# LCD_to_VGA_Modul.net
KiCad netlist of a schematic drawn in EAGLE
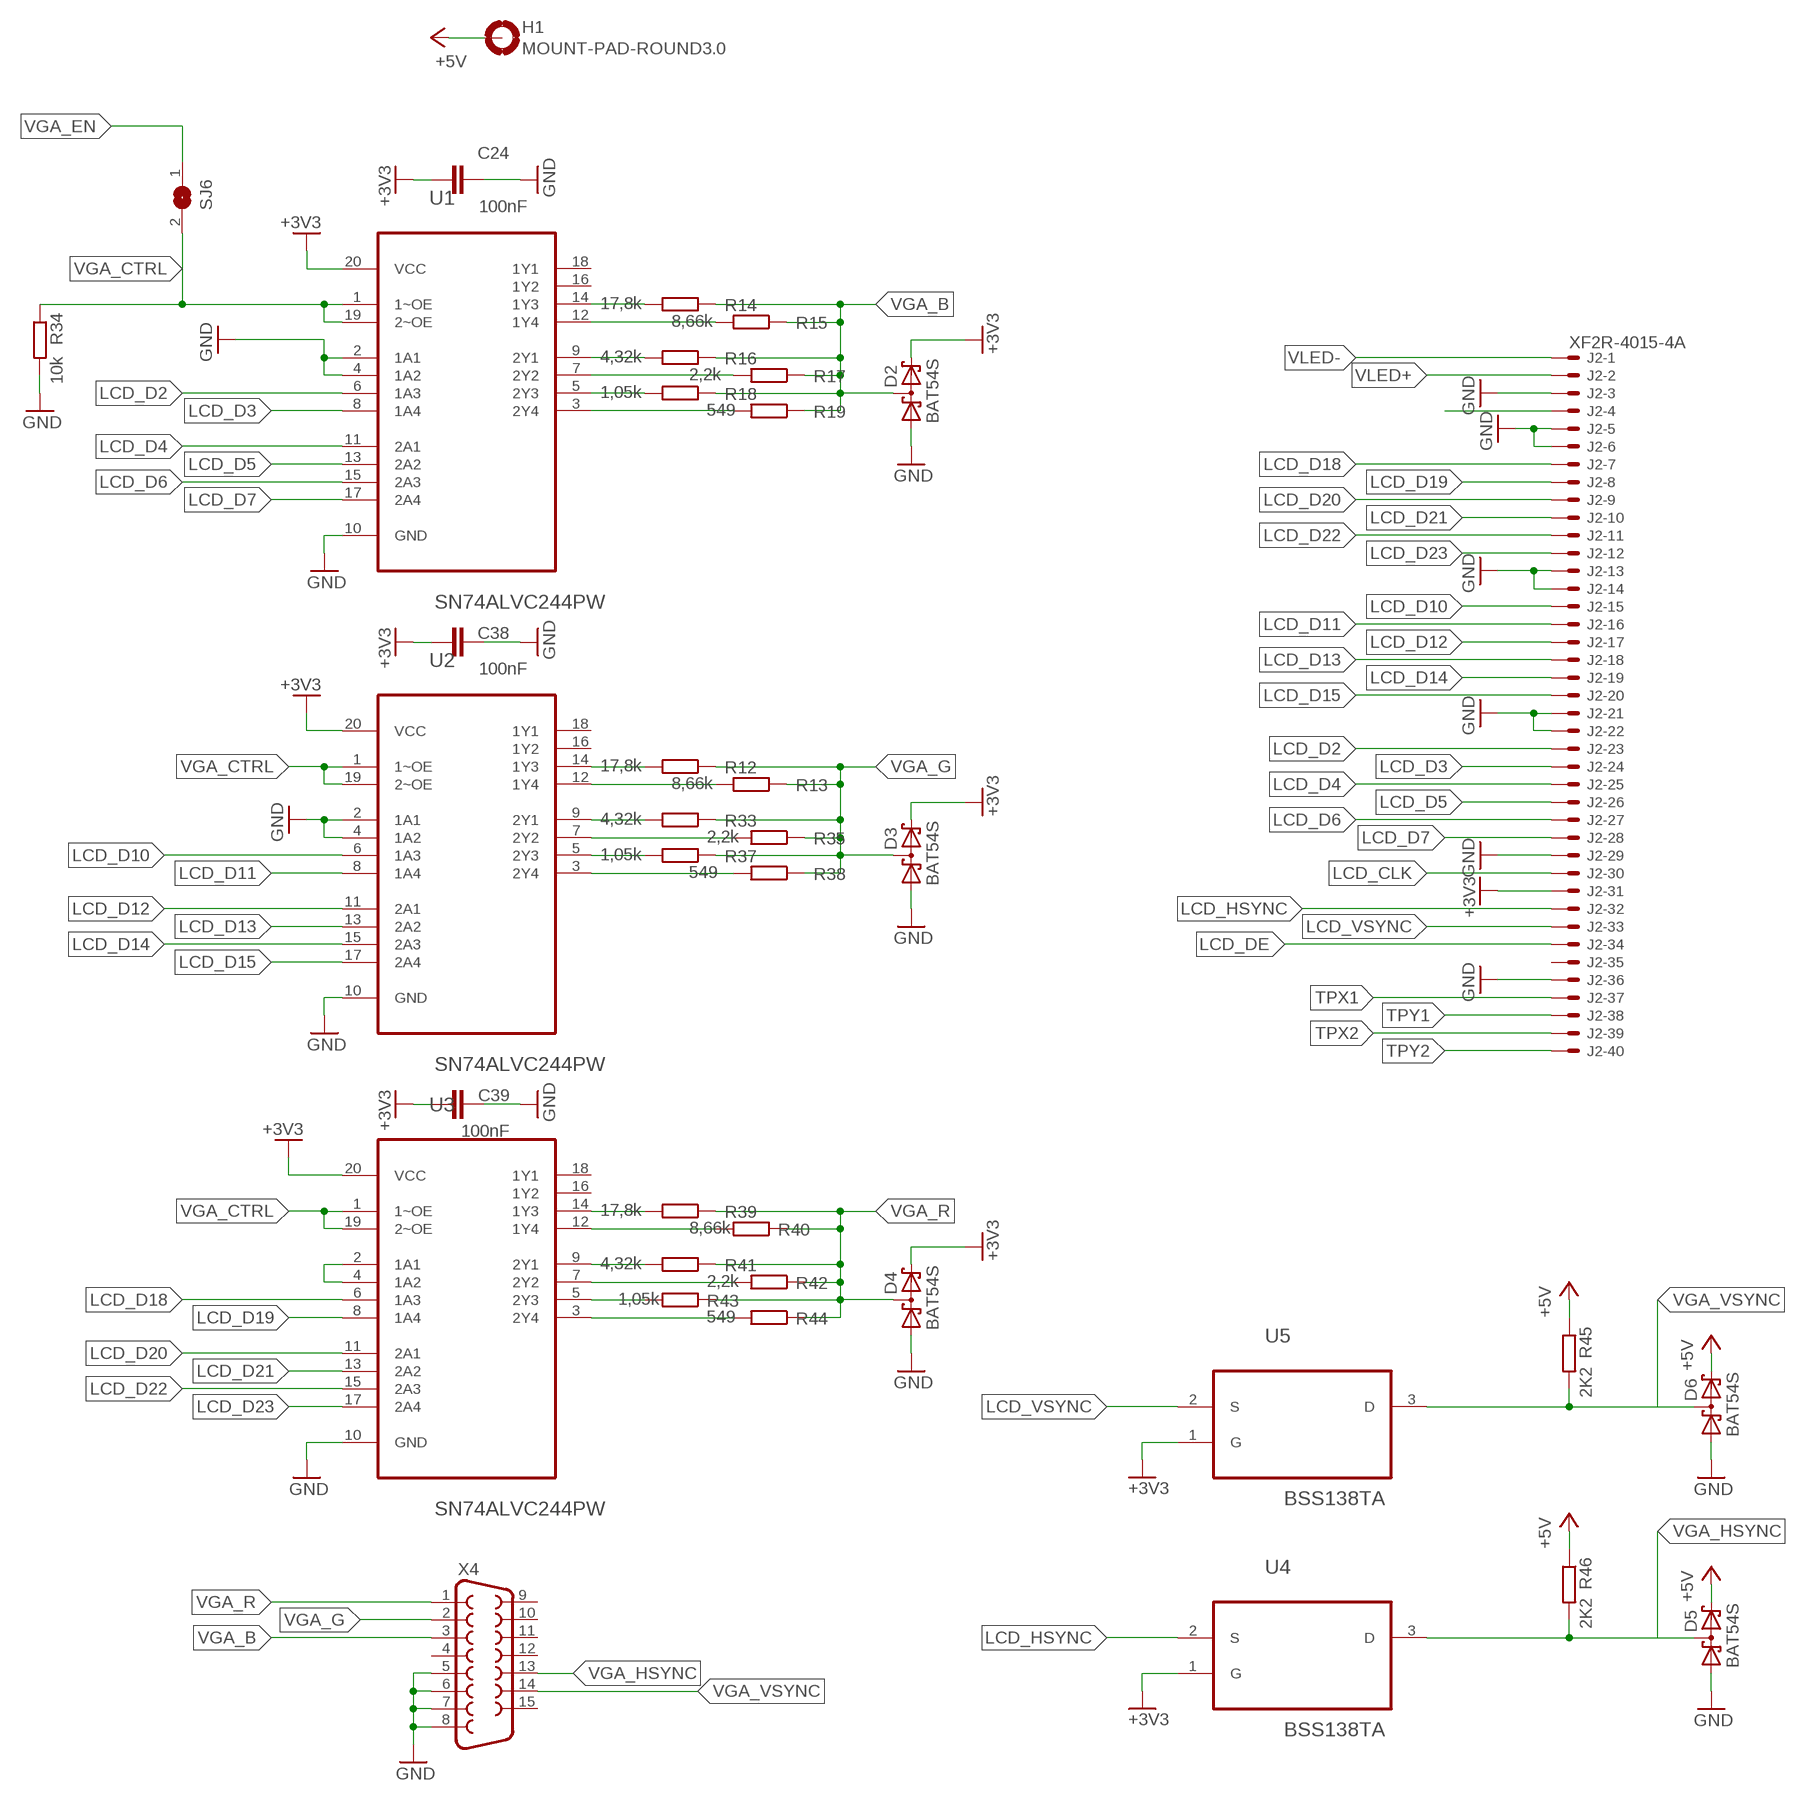
[diagram p0: schematic, sheet 1]

(export (version "E")
  (design (tool "Eeschema 10.0.6"))
  (components
    (comp (ref "C24")
      (value "100nF")
      (footprint "eagle-import:C0805")
      (libsource (lib "eagle-import") (part "C-EUC0805"))
    )
    (comp (ref "C38")
      (value "100nF")
      (footprint "eagle-import:C0805")
      (libsource (lib "eagle-import") (part "C-EUC0805"))
    )
    (comp (ref "C39")
      (value "100nF")
      (footprint "eagle-import:C0805")
      (libsource (lib "eagle-import") (part "C-EUC0805"))
    )
    (comp (ref "D2")
      (value "BAT54S")
      (footprint "eagle-import:SOT23")
      (libsource (lib "eagle-import") (part "BAT54S"))
    )
    (comp (ref "D3")
      (value "BAT54S")
      (footprint "eagle-import:SOT23")
      (libsource (lib "eagle-import") (part "BAT54S"))
    )
    (comp (ref "D4")
      (value "BAT54S")
      (footprint "eagle-import:SOT23")
      (libsource (lib "eagle-import") (part "BAT54S"))
    )
    (comp (ref "D5")
      (value "BAT54S")
      (footprint "eagle-import:SOT23")
      (libsource (lib "eagle-import") (part "BAT54S"))
    )
    (comp (ref "D6")
      (value "BAT54S")
      (footprint "eagle-import:SOT23")
      (libsource (lib "eagle-import") (part "BAT54S"))
    )
    (comp (ref "H1")
      (value "MOUNT-PAD-ROUND3.0")
      (footprint "eagle-import:3,0-PAD")
      (libsource (lib "eagle-import") (part "MOUNT-PAD-ROUND3.0"))
    )
    (comp (ref "J2")
      (value "XF2R-4015-4A")
      (footprint "eagle-import:XF2R-4015-4A")
      (libsource (lib "eagle-import") (part "XF2-40?15-4AR"))
    )
    (comp (ref "R12")
      (value "17,8k")
      (footprint "eagle-import:R0805")
      (libsource (lib "eagle-import") (part "R-EU_R0805"))
    )
    (comp (ref "R13")
      (value "8,66k")
      (footprint "eagle-import:R0805")
      (libsource (lib "eagle-import") (part "R-EU_R0805"))
    )
    (comp (ref "R14")
      (value "17,8k")
      (footprint "eagle-import:R0805")
      (libsource (lib "eagle-import") (part "R-EU_R0805"))
    )
    (comp (ref "R15")
      (value "8,66k")
      (footprint "eagle-import:R0805")
      (libsource (lib "eagle-import") (part "R-EU_R0805"))
    )
    (comp (ref "R16")
      (value "4,32k")
      (footprint "eagle-import:R0805")
      (libsource (lib "eagle-import") (part "R-EU_R0805"))
    )
    (comp (ref "R17")
      (value "2,2k")
      (footprint "eagle-import:R0805")
      (libsource (lib "eagle-import") (part "R-EU_R0805"))
    )
    (comp (ref "R18")
      (value "1,05k")
      (footprint "eagle-import:R0805")
      (libsource (lib "eagle-import") (part "R-EU_R0805"))
    )
    (comp (ref "R19")
      (value "549")
      (footprint "eagle-import:R0805")
      (libsource (lib "eagle-import") (part "R-EU_R0805"))
    )
    (comp (ref "R33")
      (value "4,32k")
      (footprint "eagle-import:R0805")
      (libsource (lib "eagle-import") (part "R-EU_R0805"))
    )
    (comp (ref "R34")
      (value "10k")
      (footprint "eagle-import:R0805")
      (libsource (lib "eagle-import") (part "R-EU_R0805"))
    )
    (comp (ref "R35")
      (value "2,2k")
      (footprint "eagle-import:R0805")
      (libsource (lib "eagle-import") (part "R-EU_R0805"))
    )
    (comp (ref "R37")
      (value "1,05k")
      (footprint "eagle-import:R0805")
      (libsource (lib "eagle-import") (part "R-EU_R0805"))
    )
    (comp (ref "R38")
      (value "549")
      (footprint "eagle-import:R0805")
      (libsource (lib "eagle-import") (part "R-EU_R0805"))
    )
    (comp (ref "R39")
      (value "17,8k")
      (footprint "eagle-import:R0805")
      (libsource (lib "eagle-import") (part "R-EU_R0805"))
    )
    (comp (ref "R40")
      (value "8,66k")
      (footprint "eagle-import:R0805")
      (libsource (lib "eagle-import") (part "R-EU_R0805"))
    )
    (comp (ref "R41")
      (value "4,32k")
      (footprint "eagle-import:R0805")
      (libsource (lib "eagle-import") (part "R-EU_R0805"))
    )
    (comp (ref "R42")
      (value "2,2k")
      (footprint "eagle-import:R0805")
      (libsource (lib "eagle-import") (part "R-EU_R0805"))
    )
    (comp (ref "R43")
      (value "1,05k")
      (footprint "eagle-import:R0805")
      (libsource (lib "eagle-import") (part "R-EU_R0805"))
    )
    (comp (ref "R44")
      (value "549")
      (footprint "eagle-import:R0805")
      (libsource (lib "eagle-import") (part "R-EU_R0805"))
    )
    (comp (ref "R45")
      (value "2K2")
      (footprint "eagle-import:R0805")
      (libsource (lib "eagle-import") (part "R-EU_R0805"))
    )
    (comp (ref "R46")
      (value "2K2")
      (footprint "eagle-import:R0805")
      (libsource (lib "eagle-import") (part "R-EU_R0805"))
    )
    (comp (ref "SJ6") (value "SJ") (footprint "eagle-import:SJ") (libsource (lib "eagle-import") (part "SJ")))
    (comp (ref "U1")
      (value "SN74ALVC244PW")
      (footprint "eagle-import:SOP65P640X120-20N")
      (libsource (lib "eagle-import") (part "SN74ALVC244PW"))
    )
    (comp (ref "U2")
      (value "SN74ALVC244PW")
      (footprint "eagle-import:SOP65P640X120-20N")
      (libsource (lib "eagle-import") (part "SN74ALVC244PW"))
    )
    (comp (ref "U3")
      (value "SN74ALVC244PW")
      (footprint "eagle-import:SOP65P640X120-20N")
      (libsource (lib "eagle-import") (part "SN74ALVC244PW"))
    )
    (comp (ref "U4")
      (value "BSS138TA")
      (footprint "eagle-import:SOT95P240X110-3N")
      (libsource (lib "eagle-import") (part "BSS138TA"))
    )
    (comp (ref "U5")
      (value "BSS138TA")
      (footprint "eagle-import:SOT95P240X110-3N")
      (libsource (lib "eagle-import") (part "BSS138TA"))
    )
    (comp (ref "X4")
      (value "F15H")
      (footprint "eagle-import:F15H")
      (libsource (lib "eagle-import") (part "F15H"))
    )
  )
  (nets
    (net (code "1") (name "+3V3") (class "Default")
      (node (ref "C24") (pin "2") (pinfunction "2_2") (pintype "passive"))
      (node (ref "C38") (pin "2") (pinfunction "2_2") (pintype "passive"))
      (node (ref "C39") (pin "2") (pinfunction "2_2") (pintype "passive"))
      (node (ref "D2") (pin "2") (pinfunction "K2_2") (pintype "passive"))
      (node (ref "D3") (pin "2") (pinfunction "K2_2") (pintype "passive"))
      (node (ref "D4") (pin "2") (pinfunction "K2_2") (pintype "passive"))
      (node (ref "J2") (pin "31") (pinfunction "MS_31") (pintype "passive"))
      (node (ref "U1") (pin "20") (pinfunction "VCC_20") (pintype "power_in"))
      (node (ref "U2") (pin "20") (pinfunction "VCC_20") (pintype "power_in"))
      (node (ref "U3") (pin "20") (pinfunction "VCC_20") (pintype "power_in"))
      (node (ref "U4") (pin "1") (pinfunction "G_1") (pintype "passive"))
      (node (ref "U5") (pin "1") (pinfunction "G_1") (pintype "passive"))
    )
    (net (code "2") (name "+5V") (class "Default")
      (node (ref "D5") (pin "2") (pinfunction "K2_2") (pintype "passive"))
      (node (ref "D6") (pin "2") (pinfunction "K2_2") (pintype "passive"))
      (node (ref "H1") (pin "B3,0") (pinfunction "MOUNT_B3,0") (pintype "passive"))
      (node (ref "R45") (pin "1") (pinfunction "1_1") (pintype "passive"))
      (node (ref "R46") (pin "1") (pinfunction "1_1") (pintype "passive"))
    )
    (net (code "3") (name "GND") (class "Default")
      (node (ref "C24") (pin "1") (pinfunction "1_1") (pintype "passive"))
      (node (ref "C38") (pin "1") (pinfunction "1_1") (pintype "passive"))
      (node (ref "C39") (pin "1") (pinfunction "1_1") (pintype "passive"))
      (node (ref "D2") (pin "1") (pinfunction "A1_1") (pintype "passive"))
      (node (ref "D3") (pin "1") (pinfunction "A1_1") (pintype "passive"))
      (node (ref "D4") (pin "1") (pinfunction "A1_1") (pintype "passive"))
      (node (ref "D5") (pin "1") (pinfunction "A1_1") (pintype "passive"))
      (node (ref "D6") (pin "1") (pinfunction "A1_1") (pintype "passive"))
      (node (ref "J2") (pin "13") (pinfunction "MS_13") (pintype "passive"))
      (node (ref "J2") (pin "14") (pinfunction "MS_14") (pintype "passive"))
      (node (ref "J2") (pin "21") (pinfunction "MS_21") (pintype "passive"))
      (node (ref "J2") (pin "22") (pinfunction "MS_22") (pintype "passive"))
      (node (ref "J2") (pin "29") (pinfunction "MS_29") (pintype "passive"))
      (node (ref "J2") (pin "3") (pinfunction "MS_3") (pintype "passive"))
      (node (ref "J2") (pin "36") (pinfunction "MS_36") (pintype "passive"))
      (node (ref "J2") (pin "5") (pinfunction "MS_5") (pintype "passive"))
      (node (ref "J2") (pin "6") (pinfunction "MS_6") (pintype "passive"))
      (node (ref "R34") (pin "2") (pinfunction "2_2") (pintype "passive"))
      (node (ref "U1") (pin "10") (pinfunction "GND_10") (pintype "passive"))
      (node (ref "U1") (pin "2") (pinfunction "1A1_2") (pintype "input"))
      (node (ref "U1") (pin "4") (pinfunction "1A2_4") (pintype "input"))
      (node (ref "U2") (pin "10") (pinfunction "GND_10") (pintype "passive"))
      (node (ref "U2") (pin "2") (pinfunction "1A1_2") (pintype "input"))
      (node (ref "U2") (pin "4") (pinfunction "1A2_4") (pintype "input"))
      (node (ref "U3") (pin "10") (pinfunction "GND_10") (pintype "passive"))
      (node (ref "X4") (pin "5") (pinfunction "5_5") (pintype "passive"))
      (node (ref "X4") (pin "6") (pinfunction "6_6") (pintype "passive"))
      (node (ref "X4") (pin "7") (pinfunction "7_7") (pintype "passive"))
      (node (ref "X4") (pin "8") (pinfunction "8_8") (pintype "passive"))
    )
    (net (code "4") (name "LCD_CLK") (class "Default")
      (node (ref "J2") (pin "30") (pinfunction "MS_30") (pintype "passive"))
    )
    (net (code "5") (name "LCD_D2") (class "Default")
      (node (ref "J2") (pin "23") (pinfunction "MS_23") (pintype "passive"))
      (node (ref "U1") (pin "6") (pinfunction "1A3_6") (pintype "input"))
    )
    (net (code "6") (name "LCD_D3") (class "Default")
      (node (ref "J2") (pin "24") (pinfunction "MS_24") (pintype "passive"))
      (node (ref "U1") (pin "8") (pinfunction "1A4_8") (pintype "input"))
    )
    (net (code "7") (name "LCD_D4") (class "Default")
      (node (ref "J2") (pin "25") (pinfunction "MS_25") (pintype "passive"))
      (node (ref "U1") (pin "11") (pinfunction "2A1_11") (pintype "input"))
    )
    (net (code "8") (name "LCD_D5") (class "Default")
      (node (ref "J2") (pin "26") (pinfunction "MS_26") (pintype "passive"))
      (node (ref "U1") (pin "13") (pinfunction "2A2_13") (pintype "input"))
    )
    (net (code "9") (name "LCD_D6") (class "Default")
      (node (ref "J2") (pin "27") (pinfunction "MS_27") (pintype "passive"))
      (node (ref "U1") (pin "15") (pinfunction "2A3_15") (pintype "input"))
    )
    (net (code "10") (name "LCD_D7") (class "Default")
      (node (ref "J2") (pin "28") (pinfunction "MS_28") (pintype "passive"))
      (node (ref "U1") (pin "17") (pinfunction "2A4_17") (pintype "input"))
    )
    (net (code "11") (name "LCD_D10") (class "Default")
      (node (ref "J2") (pin "15") (pinfunction "MS_15") (pintype "passive"))
      (node (ref "U2") (pin "6") (pinfunction "1A3_6") (pintype "input"))
    )
    (net (code "12") (name "LCD_D11") (class "Default")
      (node (ref "J2") (pin "16") (pinfunction "MS_16") (pintype "passive"))
      (node (ref "U2") (pin "8") (pinfunction "1A4_8") (pintype "input"))
    )
    (net (code "13") (name "LCD_D12") (class "Default")
      (node (ref "J2") (pin "17") (pinfunction "MS_17") (pintype "passive"))
      (node (ref "U2") (pin "11") (pinfunction "2A1_11") (pintype "input"))
    )
    (net (code "14") (name "LCD_D13") (class "Default")
      (node (ref "J2") (pin "18") (pinfunction "MS_18") (pintype "passive"))
      (node (ref "U2") (pin "13") (pinfunction "2A2_13") (pintype "input"))
    )
    (net (code "15") (name "LCD_D14") (class "Default")
      (node (ref "J2") (pin "19") (pinfunction "MS_19") (pintype "passive"))
      (node (ref "U2") (pin "15") (pinfunction "2A3_15") (pintype "input"))
    )
    (net (code "16") (name "LCD_D15") (class "Default")
      (node (ref "J2") (pin "20") (pinfunction "MS_20") (pintype "passive"))
      (node (ref "U2") (pin "17") (pinfunction "2A4_17") (pintype "input"))
    )
    (net (code "17") (name "LCD_D18") (class "Default")
      (node (ref "J2") (pin "7") (pinfunction "MS_7") (pintype "passive"))
      (node (ref "U3") (pin "6") (pinfunction "1A3_6") (pintype "input"))
    )
    (net (code "18") (name "LCD_D19") (class "Default")
      (node (ref "J2") (pin "8") (pinfunction "MS_8") (pintype "passive"))
      (node (ref "U3") (pin "8") (pinfunction "1A4_8") (pintype "input"))
    )
    (net (code "19") (name "LCD_D20") (class "Default")
      (node (ref "J2") (pin "9") (pinfunction "MS_9") (pintype "passive"))
      (node (ref "U3") (pin "11") (pinfunction "2A1_11") (pintype "input"))
    )
    (net (code "20") (name "LCD_D21") (class "Default")
      (node (ref "J2") (pin "10") (pinfunction "MS_10") (pintype "passive"))
      (node (ref "U3") (pin "13") (pinfunction "2A2_13") (pintype "input"))
    )
    (net (code "21") (name "LCD_D22") (class "Default")
      (node (ref "J2") (pin "11") (pinfunction "MS_11") (pintype "passive"))
      (node (ref "U3") (pin "15") (pinfunction "2A3_15") (pintype "input"))
    )
    (net (code "22") (name "LCD_D23") (class "Default")
      (node (ref "J2") (pin "12") (pinfunction "MS_12") (pintype "passive"))
      (node (ref "U3") (pin "17") (pinfunction "2A4_17") (pintype "input"))
    )
    (net (code "23") (name "LCD_DE") (class "Default")
      (node (ref "J2") (pin "34") (pinfunction "MS_34") (pintype "passive"))
    )
    (net (code "24") (name "LCD_HSYNC") (class "Default")
      (node (ref "J2") (pin "32") (pinfunction "MS_32") (pintype "passive"))
      (node (ref "U4") (pin "2") (pinfunction "S_2") (pintype "passive"))
    )
    (net (code "25") (name "LCD_VSYNC") (class "Default")
      (node (ref "J2") (pin "33") (pinfunction "MS_33") (pintype "passive"))
      (node (ref "U5") (pin "2") (pinfunction "S_2") (pintype "passive"))
    )
    (net (code "26") (name "Net-(U1-1Y3)") (class "Default")
      (node (ref "R14") (pin "2") (pinfunction "2_2") (pintype "passive"))
      (node (ref "U1") (pin "14") (pinfunction "1Y3_14") (pintype "output"))
    )
    (net (code "27") (name "Net-(U1-1Y4)") (class "Default")
      (node (ref "R15") (pin "2") (pinfunction "2_2") (pintype "passive"))
      (node (ref "U1") (pin "12") (pinfunction "1Y4_12") (pintype "output"))
    )
    (net (code "28") (name "Net-(U1-2Y1)") (class "Default")
      (node (ref "R16") (pin "2") (pinfunction "2_2") (pintype "passive"))
      (node (ref "U1") (pin "9") (pinfunction "2Y1_9") (pintype "output"))
    )
    (net (code "29") (name "Net-(U1-2Y2)") (class "Default")
      (node (ref "R17") (pin "2") (pinfunction "2_2") (pintype "passive"))
      (node (ref "U1") (pin "7") (pinfunction "2Y2_7") (pintype "output"))
    )
    (net (code "30") (name "Net-(U1-2Y3)") (class "Default")
      (node (ref "R18") (pin "2") (pinfunction "2_2") (pintype "passive"))
      (node (ref "U1") (pin "5") (pinfunction "2Y3_5") (pintype "output"))
    )
    (net (code "31") (name "Net-(U1-2Y4)") (class "Default")
      (node (ref "R19") (pin "2") (pinfunction "2_2") (pintype "passive"))
      (node (ref "U1") (pin "3") (pinfunction "2Y4_3") (pintype "output"))
    )
    (net (code "32") (name "Net-(U2-1Y3)") (class "Default")
      (node (ref "R12") (pin "2") (pinfunction "2_2") (pintype "passive"))
      (node (ref "U2") (pin "14") (pinfunction "1Y3_14") (pintype "output"))
    )
    (net (code "33") (name "Net-(U2-1Y4)") (class "Default")
      (node (ref "R13") (pin "2") (pinfunction "2_2") (pintype "passive"))
      (node (ref "U2") (pin "12") (pinfunction "1Y4_12") (pintype "output"))
    )
    (net (code "34") (name "Net-(U2-2Y1)") (class "Default")
      (node (ref "R33") (pin "2") (pinfunction "2_2") (pintype "passive"))
      (node (ref "U2") (pin "9") (pinfunction "2Y1_9") (pintype "output"))
    )
    (net (code "35") (name "Net-(U2-2Y2)") (class "Default")
      (node (ref "R35") (pin "2") (pinfunction "2_2") (pintype "passive"))
      (node (ref "U2") (pin "7") (pinfunction "2Y2_7") (pintype "output"))
    )
    (net (code "36") (name "Net-(U2-2Y3)") (class "Default")
      (node (ref "R37") (pin "2") (pinfunction "2_2") (pintype "passive"))
      (node (ref "U2") (pin "5") (pinfunction "2Y3_5") (pintype "output"))
    )
    (net (code "37") (name "Net-(U2-2Y4)") (class "Default")
      (node (ref "R38") (pin "2") (pinfunction "2_2") (pintype "passive"))
      (node (ref "U2") (pin "3") (pinfunction "2Y4_3") (pintype "output"))
    )
    (net (code "38") (name "Net-(U3-1A1)") (class "Default")
      (node (ref "U3") (pin "2") (pinfunction "1A1_2") (pintype "input"))
      (node (ref "U3") (pin "4") (pinfunction "1A2_4") (pintype "input"))
    )
    (net (code "39") (name "Net-(U3-1Y3)") (class "Default")
      (node (ref "R39") (pin "2") (pinfunction "2_2") (pintype "passive"))
      (node (ref "U3") (pin "14") (pinfunction "1Y3_14") (pintype "output"))
    )
    (net (code "40") (name "Net-(U3-1Y4)") (class "Default")
      (node (ref "R40") (pin "2") (pinfunction "2_2") (pintype "passive"))
      (node (ref "U3") (pin "12") (pinfunction "1Y4_12") (pintype "output"))
    )
    (net (code "41") (name "Net-(U3-2Y1)") (class "Default")
      (node (ref "R41") (pin "2") (pinfunction "2_2") (pintype "passive"))
      (node (ref "U3") (pin "9") (pinfunction "2Y1_9") (pintype "output"))
    )
    (net (code "42") (name "Net-(U3-2Y2)") (class "Default")
      (node (ref "R42") (pin "2") (pinfunction "2_2") (pintype "passive"))
      (node (ref "U3") (pin "7") (pinfunction "2Y2_7") (pintype "output"))
    )
    (net (code "43") (name "Net-(U3-2Y3)") (class "Default")
      (node (ref "R43") (pin "2") (pinfunction "2_2") (pintype "passive"))
      (node (ref "U3") (pin "5") (pinfunction "2Y3_5") (pintype "output"))
    )
    (net (code "44") (name "Net-(U3-2Y4)") (class "Default")
      (node (ref "R44") (pin "2") (pinfunction "2_2") (pintype "passive"))
      (node (ref "U3") (pin "3") (pinfunction "2Y4_3") (pintype "output"))
    )
    (net (code "45") (name "TPX1") (class "Default")
      (node (ref "J2") (pin "37") (pinfunction "MS_37") (pintype "passive"))
    )
    (net (code "46") (name "TPX2") (class "Default")
      (node (ref "J2") (pin "39") (pinfunction "MS_39") (pintype "passive"))
    )
    (net (code "47") (name "TPY1") (class "Default")
      (node (ref "J2") (pin "38") (pinfunction "MS_38") (pintype "passive"))
    )
    (net (code "48") (name "TPY2") (class "Default")
      (node (ref "J2") (pin "40") (pinfunction "MS_40") (pintype "passive"))
    )
    (net (code "49") (name "VGA_B") (class "Default")
      (node (ref "D2") (pin "3") (pinfunction "K1A2_3") (pintype "passive"))
      (node (ref "R14") (pin "1") (pinfunction "1_1") (pintype "passive"))
      (node (ref "R15") (pin "1") (pinfunction "1_1") (pintype "passive"))
      (node (ref "R16") (pin "1") (pinfunction "1_1") (pintype "passive"))
      (node (ref "R17") (pin "1") (pinfunction "1_1") (pintype "passive"))
      (node (ref "R18") (pin "1") (pinfunction "1_1") (pintype "passive"))
      (node (ref "R19") (pin "1") (pinfunction "1_1") (pintype "passive"))
      (node (ref "X4") (pin "3") (pinfunction "3_3") (pintype "passive"))
    )
    (net (code "50") (name "VGA_CTRL") (class "Default")
      (node (ref "R34") (pin "1") (pinfunction "1_1") (pintype "passive"))
      (node (ref "SJ6") (pin "2") (pinfunction "2_2") (pintype "passive"))
      (node (ref "U1") (pin "1") (pinfunction "1~{OE}_1") (pintype "input"))
      (node (ref "U1") (pin "19") (pinfunction "2~{OE}_19") (pintype "input"))
      (node (ref "U2") (pin "1") (pinfunction "1~{OE}_1") (pintype "input"))
      (node (ref "U2") (pin "19") (pinfunction "2~{OE}_19") (pintype "input"))
      (node (ref "U3") (pin "1") (pinfunction "1~{OE}_1") (pintype "input"))
      (node (ref "U3") (pin "19") (pinfunction "2~{OE}_19") (pintype "input"))
    )
    (net (code "51") (name "VGA_EN") (class "Default")
      (node (ref "SJ6") (pin "1") (pinfunction "1_1") (pintype "passive"))
    )
    (net (code "52") (name "VGA_G") (class "Default")
      (node (ref "D3") (pin "3") (pinfunction "K1A2_3") (pintype "passive"))
      (node (ref "R12") (pin "1") (pinfunction "1_1") (pintype "passive"))
      (node (ref "R13") (pin "1") (pinfunction "1_1") (pintype "passive"))
      (node (ref "R33") (pin "1") (pinfunction "1_1") (pintype "passive"))
      (node (ref "R35") (pin "1") (pinfunction "1_1") (pintype "passive"))
      (node (ref "R37") (pin "1") (pinfunction "1_1") (pintype "passive"))
      (node (ref "R38") (pin "1") (pinfunction "1_1") (pintype "passive"))
      (node (ref "X4") (pin "2") (pinfunction "2_2") (pintype "passive"))
    )
    (net (code "53") (name "VGA_HSYNC") (class "Default")
      (node (ref "D5") (pin "3") (pinfunction "K1A2_3") (pintype "passive"))
      (node (ref "R46") (pin "2") (pinfunction "2_2") (pintype "passive"))
      (node (ref "U4") (pin "3") (pinfunction "D_3") (pintype "passive"))
      (node (ref "X4") (pin "13") (pinfunction "13_13") (pintype "passive"))
    )
    (net (code "54") (name "VGA_R") (class "Default")
      (node (ref "D4") (pin "3") (pinfunction "K1A2_3") (pintype "passive"))
      (node (ref "R39") (pin "1") (pinfunction "1_1") (pintype "passive"))
      (node (ref "R40") (pin "1") (pinfunction "1_1") (pintype "passive"))
      (node (ref "R41") (pin "1") (pinfunction "1_1") (pintype "passive"))
      (node (ref "R42") (pin "1") (pinfunction "1_1") (pintype "passive"))
      (node (ref "R43") (pin "1") (pinfunction "1_1") (pintype "passive"))
      (node (ref "R44") (pin "1") (pinfunction "1_1") (pintype "passive"))
      (node (ref "X4") (pin "1") (pinfunction "1_1") (pintype "passive"))
    )
    (net (code "55") (name "VGA_VSYNC") (class "Default")
      (node (ref "D6") (pin "3") (pinfunction "K1A2_3") (pintype "passive"))
      (node (ref "R45") (pin "2") (pinfunction "2_2") (pintype "passive"))
      (node (ref "U5") (pin "3") (pinfunction "D_3") (pintype "passive"))
      (node (ref "X4") (pin "14") (pinfunction "14_14") (pintype "passive"))
    )
    (net (code "56") (name "VLED+") (class "Default")
      (node (ref "J2") (pin "2") (pinfunction "MS_2") (pintype "passive"))
    )
    (net (code "57") (name "VLED-") (class "Default")
      (node (ref "J2") (pin "1") (pinfunction "MSV_1") (pintype "passive"))
    )
    (net (code "58") (name "unconnected-(J2AC-MS-Pad35)") (class "Default")
      (node (ref "J2") (pin "35") (pinfunction "MS_35") (pintype "passive"))
    )
    (net (code "59") (name "unconnected-(J2AH-MS-Pad4)") (class "Default")
      (node (ref "J2") (pin "4") (pinfunction "MS_4") (pintype "passive"))
    )
    (net (code "60") (name "unconnected-(U1-1Y1-Pad18)") (class "Default")
      (node (ref "U1") (pin "18") (pinfunction "1Y1_18") (pintype "output"))
    )
    (net (code "61") (name "unconnected-(U1-1Y2-Pad16)") (class "Default")
      (node (ref "U1") (pin "16") (pinfunction "1Y2_16") (pintype "output"))
    )
    (net (code "62") (name "unconnected-(U2-1Y1-Pad18)") (class "Default")
      (node (ref "U2") (pin "18") (pinfunction "1Y1_18") (pintype "output"))
    )
    (net (code "63") (name "unconnected-(U2-1Y2-Pad16)") (class "Default")
      (node (ref "U2") (pin "16") (pinfunction "1Y2_16") (pintype "output"))
    )
    (net (code "64") (name "unconnected-(U3-1Y1-Pad18)") (class "Default")
      (node (ref "U3") (pin "18") (pinfunction "1Y1_18") (pintype "output"))
    )
    (net (code "65") (name "unconnected-(U3-1Y2-Pad16)") (class "Default")
      (node (ref "U3") (pin "16") (pinfunction "1Y2_16") (pintype "output"))
    )
    (net (code "66") (name "unconnected-(X4-Pad4)") (class "Default")
      (node (ref "X4") (pin "4") (pinfunction "4_4") (pintype "passive"))
    )
    (net (code "67") (name "unconnected-(X4-Pad9)") (class "Default")
      (node (ref "X4") (pin "9") (pinfunction "9_9") (pintype "passive"))
    )
    (net (code "68") (name "unconnected-(X4-Pad10)") (class "Default")
      (node (ref "X4") (pin "10") (pinfunction "10_10") (pintype "passive"))
    )
    (net (code "69") (name "unconnected-(X4-Pad11)") (class "Default")
      (node (ref "X4") (pin "11") (pinfunction "11_11") (pintype "passive"))
    )
    (net (code "70") (name "unconnected-(X4-Pad12)") (class "Default")
      (node (ref "X4") (pin "12") (pinfunction "12_12") (pintype "passive"))
    )
    (net (code "71") (name "unconnected-(X4-Pad15)") (class "Default")
      (node (ref "X4") (pin "15") (pinfunction "15_15") (pintype "passive"))
    )
  )
)
